# LM2596PowerLayer.net
KiCad netlist of a schematic drawn in Altium Designer
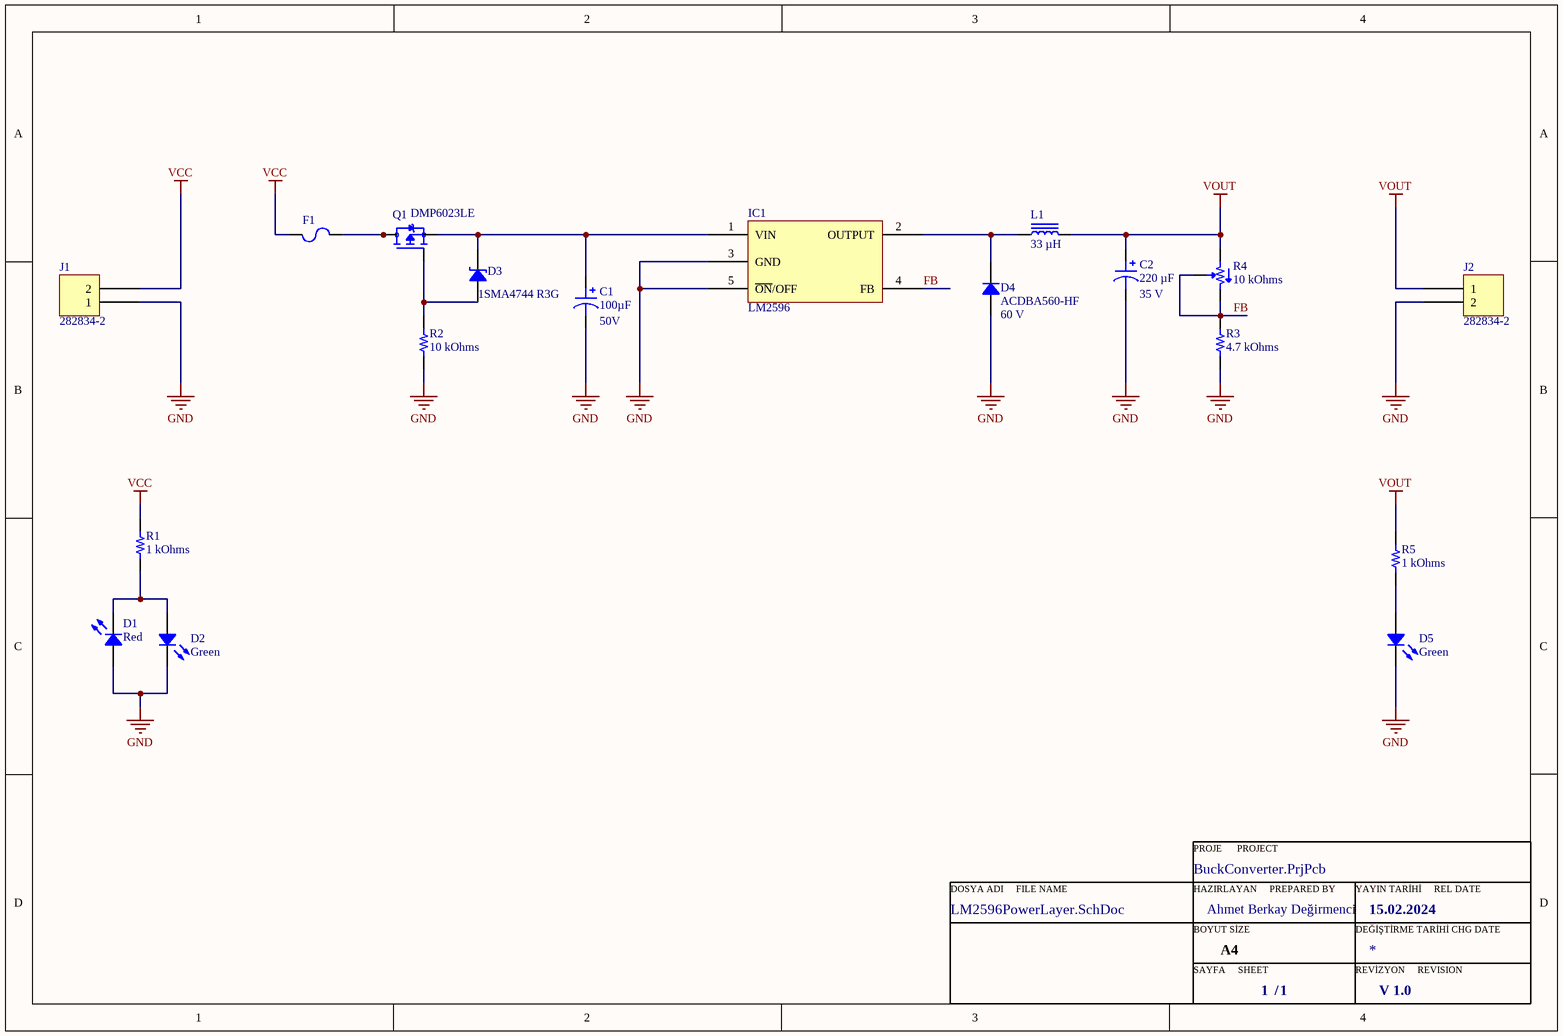
[diagram p0: LM2596PowerLayer.SchDoc]

(export (version "E")
  (design (tool "Eeschema 10.0.6"))
  (components
    (comp (ref "C1")
      (value "100µF")
      (footprint "CAP ALSMD 8.3MM H10.5MM")
      (description "CAP ALUM 100UF 20% 50V SMD")
      (fields
        (field (name "PART NUMBER") "UUR1H101MNL6GS")
        (field (name "MANUFACTURER") "Nichicon")
        (field (name "VOLTAGE - RATED") "50V")
      )
      (libsource (lib "Celestial Altium Library - altium_library") (part "Polarised Capacitor"))
    )
    (comp (ref "C2")
      (value "220 µF")
      (footprint "CAP ALSMD 8.3MM H10.5MM")
      (description "CAP ALUM 220UF 20% 35V SMD")
      (fields
        (field (name "PART NUMBER") "35TZV220M8X10.5")
        (field (name "MANUFACTURER") "Rubycon")
        (field (name "VOLTAGE - RATED") "35 V")
      )
      (libsource (lib "Celestial Altium Library - altium_library") (part "Polarised Capacitor"))
    )
    (comp (ref "D1")
      (value "Red")
      (footprint "LED 0805_2012 RED")
      (description "LED RED 0805 SMD")
      (fields (field (name "PART NUMBER") "5990110007F") (field (name "MANUFACTURER") "Dialight"))
      (libsource (lib "Celestial Altium Library - altium_library") (part "LED"))
    )
    (comp (ref "D2")
      (value "Green")
      (footprint "LED 0805_2012 GREEN")
      (description "LED GREEN CLEAR CHIP SMD")
      (fields (field (name "PART NUMBER") "APHCM2012CGCK-F01") (field (name "MANUFACTURER") "Kingbright"))
      (libsource (lib "Celestial Altium Library - altium_library") (part "LED"))
    )
    (comp (ref "D3")
      (value "1SMA4744 R3G")
      (footprint "DO214AC SMA")
      (description "DIODE ZENER 15V 1.25W DO214AC")
      (fields
        (field (name "MANUFACTURER") "Taiwan Semiconductor Corporation")
        (field (name "TOLERANCE") "±5%")
      )
      (libsource (lib "Celestial Altium Library - altium_library") (part "Diode Zener"))
    )
    (comp (ref "D4")
      (value "ACDBA560-HF")
      (footprint "DO214AC SMA")
      (description "DIODE SCHOTTKY 60V 5A DO214AC")
      (fields
        (field (name "MANUFACTURER") "Comchip Technology")
        (field (name "VOLTAGE - DC REVERSE (VR) (MAX)") "60 V")
      )
      (libsource (lib "Celestial Altium Library - altium_library") (part "Diode"))
    )
    (comp (ref "D5")
      (value "Green")
      (footprint "LED 0805_2012 GREEN")
      (description "LED GREEN CLEAR CHIP SMD")
      (fields (field (name "PART NUMBER") "APHCM2012CGCK-F01") (field (name "MANUFACTURER") "Kingbright"))
      (libsource (lib "Celestial Altium Library - altium_library") (part "LED"))
    )
    (comp (ref "F1")
      (value "~")
      (footprint "FUSE 1206_3216 0.6MM")
      (description "FUSE BOARD MOUNT 4A 63VDC 1206")
      (fields
        (field (name "PART NUMBER") "MFU1206FF04000P100")
        (field (name "MANUFACTURER") "Vishay Beyschlag")
      )
      (libsource (lib "Celestial Altium Library - altium_library") (part "MOUNTED FUSE"))
    )
    (comp (ref "IC1") (value "LM2596") (footprint "D2PAK") (libsource (lib "AltiumBuck") (part "LM2596")))
    (comp (ref "J1")
      (value "282834-2")
      (footprint "TE 282834-2")
      (description "TERM BLK 2P SIDE ENT 2.54MM PCB")
      (fields (field (name "MANUFACTURER") "TE Connectivity AMP Connectors") (field (name "VOLTAGE") "150V"))
      (libsource (lib "") (part "2 Pin_1"))
    )
    (comp (ref "J2")
      (value "282834-2")
      (footprint "TE 282834-2")
      (description "TERM BLK 2P SIDE ENT 2.54MM PCB")
      (fields (field (name "MANUFACTURER") "TE Connectivity AMP Connectors") (field (name "VOLTAGE") "150V"))
      (libsource (lib "Celestial Altium Library - altium_library") (part "2 Pin"))
    )
    (comp (ref "L1")
      (value "33 µH")
      (footprint "BOURNS SRR1280")
      (description "FIXED IND 33UH 3.5A 57 MOHM SMD")
      (fields (field (name "PART NUMBER") "SRR1280-330M") (field (name "MANUFACTURER") "Bourns Inc."))
      (libsource (lib "Celestial Altium Library - altium_library") (part "Inductor"))
    )
    (comp (ref "Q1")
      (value "DMP6023LE")
      (footprint "SOT223")
      (description "Case: SOT223")
      (libsource (lib "AltiumBuck") (part "DMP6023LE"))
    )
    (comp (ref "R1")
      (value "1 kOhms")
      (footprint "RES 0805_2012")
      (description "RES SMD 1K OHM 5% 1/8W 0805")
      (fields (field (name "PART NUMBER") "CRCW08051K00JNEAIF") (field (name "MANUFACTURER") "Vishay Dale"))
      (libsource (lib "Celestial Altium Library - altium_library") (part "Resistor"))
    )
    (comp (ref "R2")
      (value "10 kOhms")
      (footprint "RES 0805_2012")
      (description "RES 10K OHM 5% 1/4W 0805 WIDE")
      (fields (field (name "PART NUMBER") "LTR10EZPJ103") (field (name "MANUFACTURER") "Rohm Semiconductor"))
      (libsource (lib "Celestial Altium Library - altium_library") (part "Resistor"))
    )
    (comp (ref "R3")
      (value "4.7 kOhms")
      (footprint "RES 0805_2012")
      (description "RES 4.7K OHM 1% 1/8W 0805")
      (fields
        (field (name "PART NUMBER") "RN73R2ATTD4701F50")
        (field (name "MANUFACTURER") "KOA Speer Electronics, Inc.")
      )
      (libsource (lib "Celestial Altium Library - altium_library") (part "Resistor"))
    )
    (comp (ref "R4")
      (value "10 kOhms")
      (footprint "BOURNS TRIMPOT 3296W")
      (description "TRIMMER 10K OHM 0.5W PC PIN TOP")
      (fields (field (name "PART NUMBER") "3296W-1-103") (field (name "MANUFACTURER") "Bourns Inc."))
      (libsource (lib "Celestial Altium Library - altium_library") (part "Potentiometer"))
    )
    (comp (ref "R5")
      (value "1 kOhms")
      (footprint "RES 0805_2012")
      (description "RES SMD 1K OHM 5% 1/8W 0805")
      (fields (field (name "PART NUMBER") "CRCW08051K00JNEAIF") (field (name "MANUFACTURER") "Vishay Dale"))
      (libsource (lib "Celestial Altium Library - altium_library") (part "Resistor"))
    )
  )
  (nets
    (net (code "1") (name "/FB") (class "Default")
      (node (ref "IC1") (pin "4") (pinfunction "FB_4") (pintype "passive"))
      (node (ref "R3") (pin "1") (pinfunction "1_1") (pintype "passive"))
      (node (ref "R4") (pin "2") (pinfunction "2_2") (pintype "passive"))
      (node (ref "R4") (pin "3") (pinfunction "3_3") (pintype "passive"))
    )
    (net (code "2") (name "GND") (class "Default")
      (node (ref "C1") (pin "2") (pinfunction "2_2") (pintype "passive"))
      (node (ref "C2") (pin "2") (pinfunction "2_2") (pintype "passive"))
      (node (ref "D1") (pin "1") (pinfunction "1_1") (pintype "passive"))
      (node (ref "D2") (pin "2") (pinfunction "2_2") (pintype "passive"))
      (node (ref "D4") (pin "1") (pinfunction "1_1") (pintype "passive"))
      (node (ref "D5") (pin "2") (pinfunction "2_2") (pintype "passive"))
      (node (ref "IC1") (pin "3") (pinfunction "GND_3") (pintype "passive"))
      (node (ref "IC1") (pin "5") (pinfunction "~{ON}/OFF_5") (pintype "passive"))
      (node (ref "J1") (pin "1") (pinfunction "1_1") (pintype "passive"))
      (node (ref "J2") (pin "2") (pinfunction "2_2") (pintype "passive"))
      (node (ref "R2") (pin "1") (pinfunction "1_1") (pintype "passive"))
      (node (ref "R3") (pin "2") (pinfunction "2_2") (pintype "passive"))
    )
    (net (code "3") (name "Net-(D1-Pad2)") (class "Default")
      (node (ref "D1") (pin "2") (pinfunction "2_2") (pintype "passive"))
      (node (ref "D2") (pin "1") (pinfunction "1_1") (pintype "passive"))
      (node (ref "R1") (pin "1") (pinfunction "1_1") (pintype "passive"))
    )
    (net (code "4") (name "Net-(D5-Pad1)") (class "Default")
      (node (ref "D5") (pin "1") (pinfunction "1_1") (pintype "passive"))
      (node (ref "R5") (pin "1") (pinfunction "1_1") (pintype "passive"))
    )
    (net (code "5") (name "Net-(F1-Pad2)") (class "Default")
      (node (ref "F1") (pin "2") (pintype "passive"))
      (node (ref "Q1") (pin "2") (pinfunction "D_2") (pintype "passive"))
      (node (ref "Q1") (pin "4") (pinfunction "D_4") (pintype "passive"))
    )
    (net (code "6") (name "Net-(IC1-OUTPUT)") (class "Default")
      (node (ref "D4") (pin "2") (pinfunction "2_2") (pintype "passive"))
      (node (ref "IC1") (pin "2") (pinfunction "OUTPUT_2") (pintype "passive"))
      (node (ref "L1") (pin "1") (pinfunction "1_1") (pintype "passive"))
    )
    (net (code "7") (name "Net-(IC1-VIN)") (class "Default")
      (node (ref "C1") (pin "1") (pinfunction "1_1") (pintype "passive"))
      (node (ref "D3") (pin "2") (pinfunction "2_2") (pintype "passive"))
      (node (ref "IC1") (pin "1") (pinfunction "VIN_1") (pintype "passive"))
      (node (ref "Q1") (pin "3") (pinfunction "S_3") (pintype "passive"))
    )
    (net (code "8") (name "Net-(Q1-G)") (class "Default")
      (node (ref "D3") (pin "1") (pinfunction "1_1") (pintype "passive"))
      (node (ref "Q1") (pin "1") (pinfunction "G_1") (pintype "passive"))
      (node (ref "R2") (pin "2") (pinfunction "2_2") (pintype "passive"))
    )
    (net (code "9") (name "VCC") (class "Default")
      (node (ref "F1") (pin "1") (pintype "passive"))
      (node (ref "J1") (pin "2") (pinfunction "2_2") (pintype "passive"))
      (node (ref "R1") (pin "2") (pinfunction "2_2") (pintype "passive"))
    )
    (net (code "10") (name "VOUT") (class "Default")
      (node (ref "C2") (pin "1") (pinfunction "1_1") (pintype "passive"))
      (node (ref "J2") (pin "1") (pinfunction "1_1") (pintype "passive"))
      (node (ref "L1") (pin "2") (pinfunction "2_2") (pintype "passive"))
      (node (ref "R4") (pin "1") (pinfunction "1_1") (pintype "passive"))
      (node (ref "R5") (pin "2") (pinfunction "2_2") (pintype "passive"))
    )
  )
)
